# SheetPIC80_A9387.net
KiCad netlist of a schematic drawn in Altium Designer
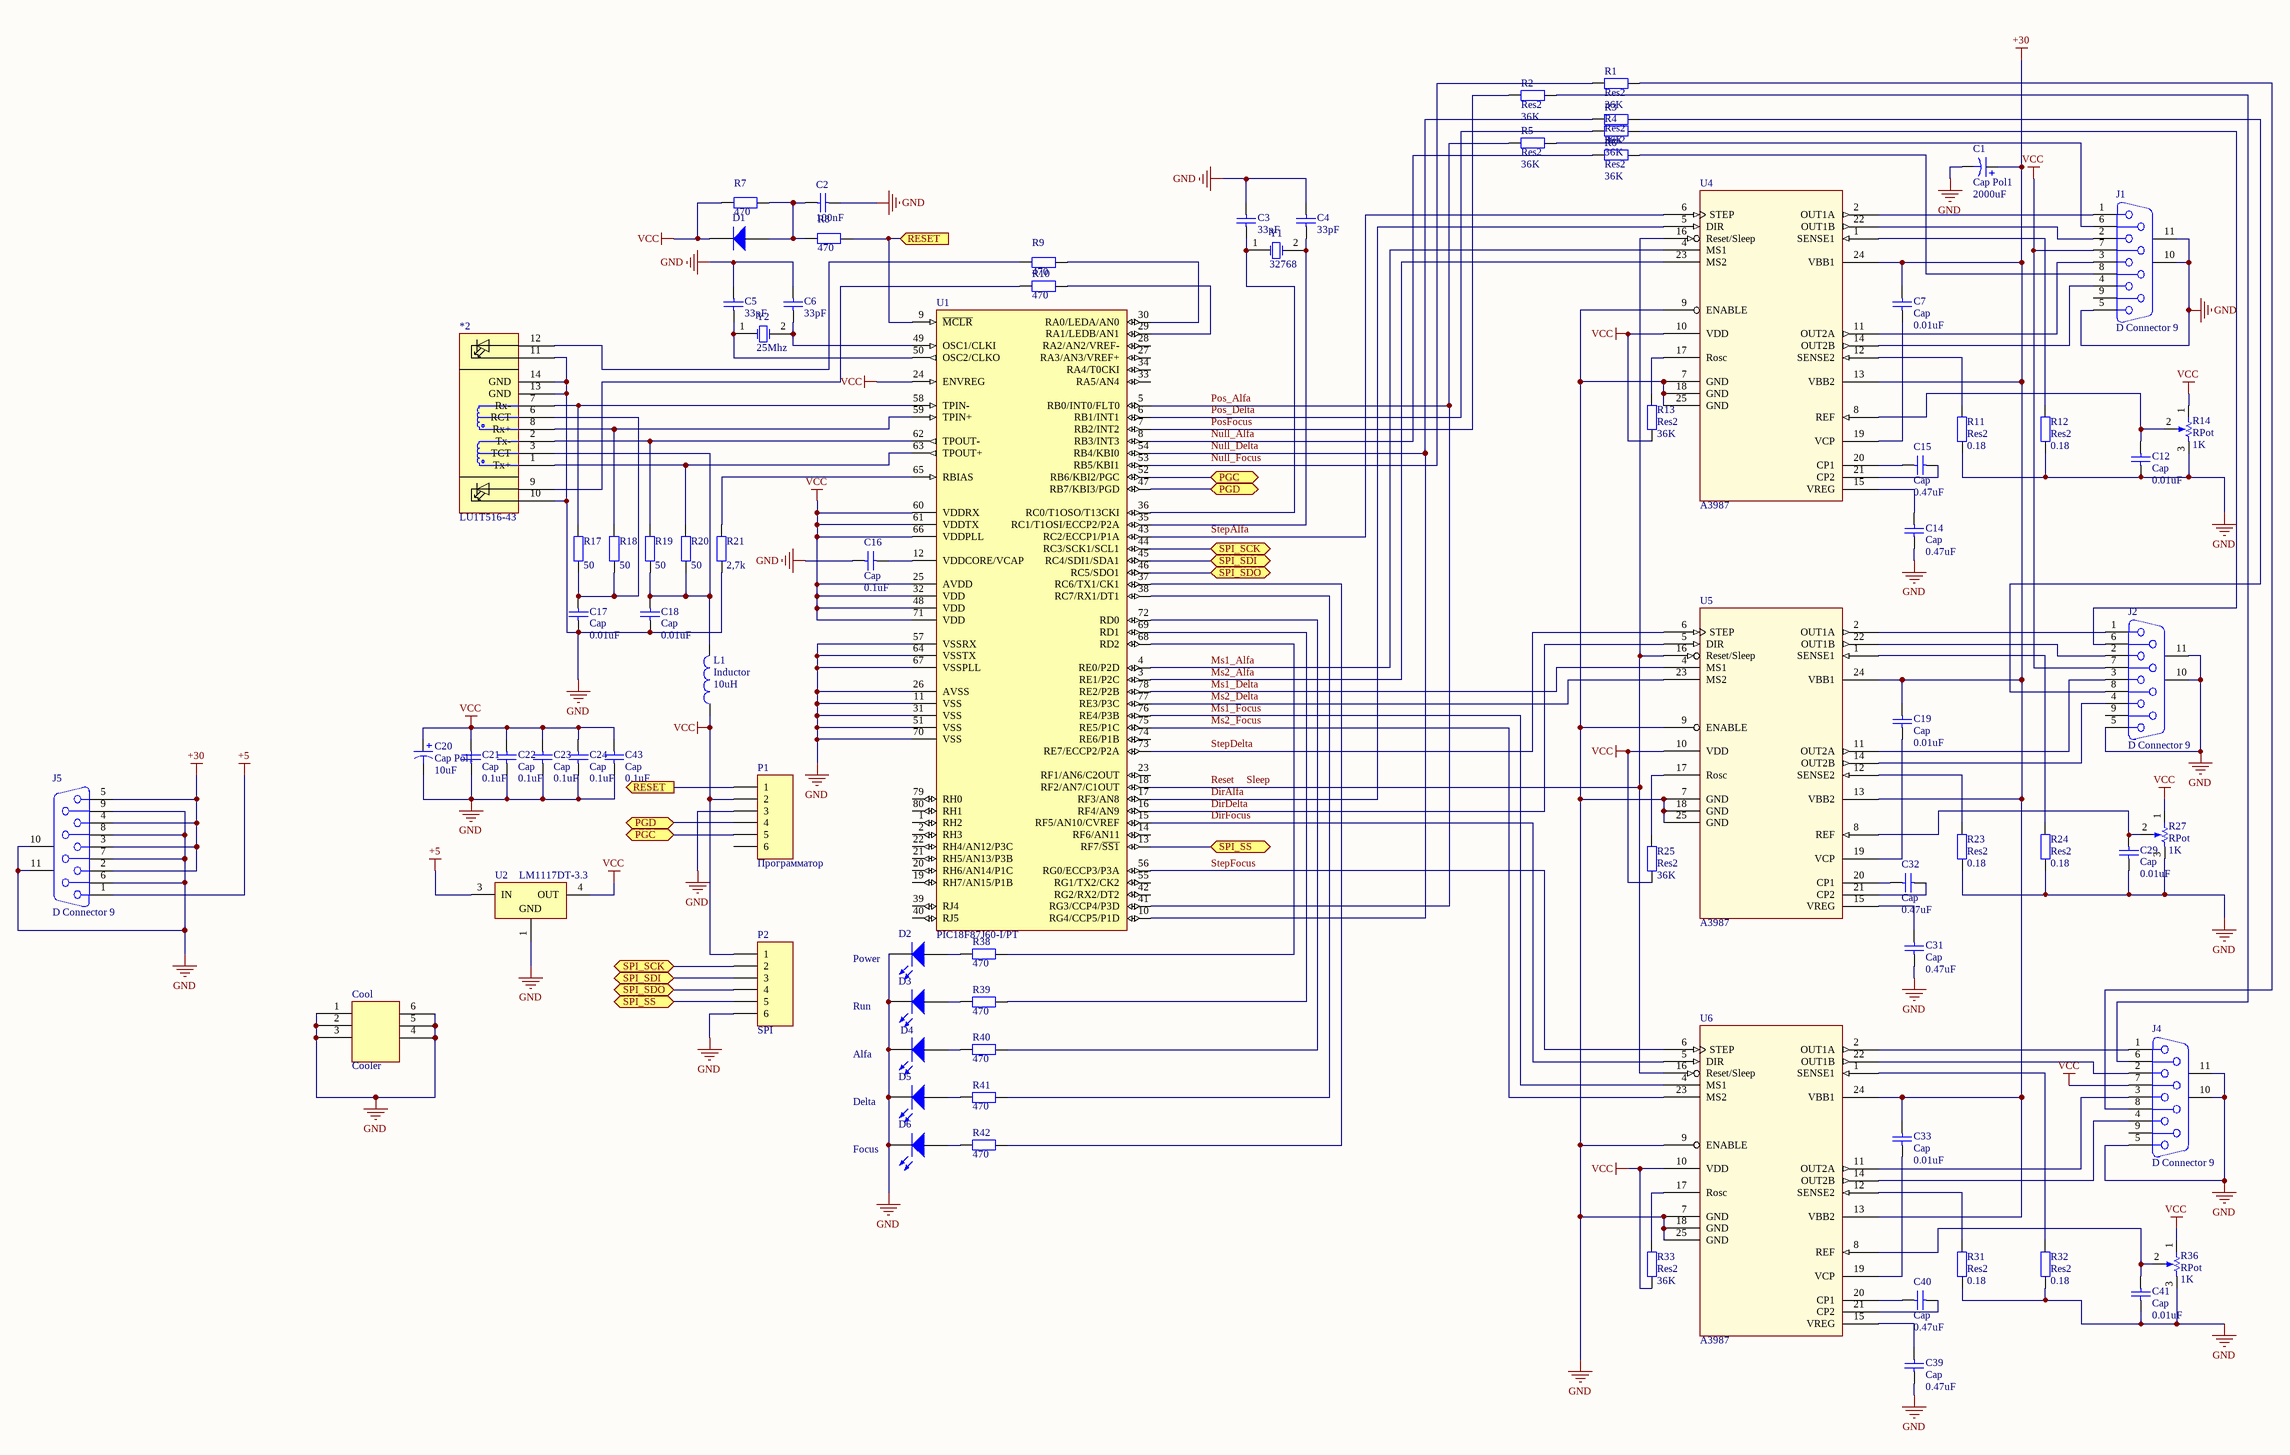
[diagram p0: SheetPIC80_A9387.SchDoc]

(export (version "E")
  (design (tool "Eeschema 10.0.6"))
  (components
    (comp (ref "*2")
      (value "LU1T516-43")
      (footprint "EthernetCON")
      (libsource (lib "Ethernet") (part "LU1T516-43"))
    )
    (comp (ref "C1")
      (value "Cap Pol1")
      (footprint "RB7.6-15")
      (description "Polarized Capacitor (Radial)")
      (fields (field (name "ALTIUM_VALUE") "2000uF"))
      (libsource (lib "Miscellaneous Devices") (part "Cap Pol1"))
    )
    (comp (ref "C2")
      (value "100nF")
      (footprint "CAPC3225N")
      (description "Capacitor")
      (fields (field (name "Comment") "Cap"))
      (libsource (lib "Miscellaneous Devices") (part "Cap"))
    )
    (comp (ref "C3")
      (value "33pF")
      (footprint "CAPC2012L")
      (description "Capacitor")
      (fields (field (name "Comment") "Cap"))
      (libsource (lib "Miscellaneous Devices") (part "Cap"))
    )
    (comp (ref "C4")
      (value "33pF")
      (footprint "CAPC2012L")
      (description "Capacitor")
      (fields (field (name "Comment") "Cap"))
      (libsource (lib "Miscellaneous Devices") (part "Cap"))
    )
    (comp (ref "C5")
      (value "33pF")
      (footprint "CAPC2012L")
      (description "Capacitor")
      (fields (field (name "Comment") "Cap"))
      (libsource (lib "Miscellaneous Devices") (part "Cap"))
    )
    (comp (ref "C6")
      (value "33pF")
      (footprint "CAPC2012L")
      (description "Capacitor")
      (fields (field (name "Comment") "Cap"))
      (libsource (lib "Miscellaneous Devices") (part "Cap"))
    )
    (comp (ref "C7")
      (value "Cap")
      (footprint "RESC3225L")
      (description "Capacitor")
      (fields (field (name "ALTIUM_VALUE") "0.01uF"))
      (libsource (lib "Miscellaneous Devices") (part "Cap"))
    )
    (comp (ref "C12")
      (value "Cap")
      (footprint "CAPC2012L")
      (description "Capacitor")
      (fields (field (name "ALTIUM_VALUE") "0.01uF"))
      (libsource (lib "Miscellaneous Devices") (part "Cap"))
    )
    (comp (ref "C14")
      (value "Cap")
      (footprint "RESC3225L")
      (description "Capacitor")
      (fields (field (name "ALTIUM_VALUE") "0.47uF"))
      (libsource (lib "Miscellaneous Devices") (part "Cap"))
    )
    (comp (ref "C15")
      (value "Cap")
      (footprint "RESC3225L")
      (description "Capacitor")
      (fields (field (name "ALTIUM_VALUE") "0.47uF"))
      (libsource (lib "Miscellaneous Devices") (part "Cap"))
    )
    (comp (ref "C16")
      (value "Cap")
      (footprint "CAPC3225L")
      (description "Capacitor")
      (fields (field (name "ALTIUM_VALUE") "0.1uF"))
      (libsource (lib "Miscellaneous Devices") (part "Cap"))
    )
    (comp (ref "C17")
      (value "Cap")
      (footprint "CAPC3216L")
      (description "Capacitor")
      (fields (field (name "ALTIUM_VALUE") "0.01uF"))
      (libsource (lib "Miscellaneous Devices") (part "Cap"))
    )
    (comp (ref "C18")
      (value "Cap")
      (footprint "CAPC3216L")
      (description "Capacitor")
      (fields (field (name "ALTIUM_VALUE") "0.01uF"))
      (libsource (lib "Miscellaneous Devices") (part "Cap"))
    )
    (comp (ref "C19")
      (value "Cap")
      (footprint "RESC3225L")
      (description "Capacitor")
      (fields (field (name "ALTIUM_VALUE") "0.01uF"))
      (libsource (lib "Miscellaneous Devices") (part "Cap"))
    )
    (comp (ref "C20")
      (value "Cap Pol1")
      (footprint "CAPPR5-5x5")
      (description "Polarized Capacitor (Radial)")
      (fields (field (name "ALTIUM_VALUE") "10uF"))
      (libsource (lib "Miscellaneous Devices") (part "Cap Pol1"))
    )
    (comp (ref "C21")
      (value "Cap")
      (footprint "CAPC3225L")
      (description "Capacitor")
      (fields (field (name "ALTIUM_VALUE") "0.1uF"))
      (libsource (lib "Miscellaneous Devices") (part "Cap"))
    )
    (comp (ref "C22")
      (value "Cap")
      (footprint "CAPC3225L")
      (description "Capacitor")
      (fields (field (name "ALTIUM_VALUE") "0.1uF"))
      (libsource (lib "Miscellaneous Devices") (part "Cap"))
    )
    (comp (ref "C23")
      (value "Cap")
      (footprint "CAPC3225L")
      (description "Capacitor")
      (fields (field (name "ALTIUM_VALUE") "0.1uF"))
      (libsource (lib "Miscellaneous Devices") (part "Cap"))
    )
    (comp (ref "C24")
      (value "Cap")
      (footprint "CAPC3225L")
      (description "Capacitor")
      (fields (field (name "ALTIUM_VALUE") "0.1uF"))
      (libsource (lib "Miscellaneous Devices") (part "Cap"))
    )
    (comp (ref "C29")
      (value "Cap")
      (footprint "CAPC2012L")
      (description "Capacitor")
      (fields (field (name "ALTIUM_VALUE") "0.01uF"))
      (libsource (lib "Miscellaneous Devices") (part "Cap"))
    )
    (comp (ref "C31")
      (value "Cap")
      (footprint "RESC3225L")
      (description "Capacitor")
      (fields (field (name "ALTIUM_VALUE") "0.47uF"))
      (libsource (lib "Miscellaneous Devices") (part "Cap"))
    )
    (comp (ref "C32")
      (value "Cap")
      (footprint "RESC3225L")
      (description "Capacitor")
      (fields (field (name "ALTIUM_VALUE") "0.47uF"))
      (libsource (lib "Miscellaneous Devices") (part "Cap"))
    )
    (comp (ref "C33")
      (value "Cap")
      (footprint "RESC3225L")
      (description "Capacitor")
      (fields (field (name "ALTIUM_VALUE") "0.01uF"))
      (libsource (lib "Miscellaneous Devices") (part "Cap"))
    )
    (comp (ref "C39")
      (value "Cap")
      (footprint "RESC3225L")
      (description "Capacitor")
      (fields (field (name "ALTIUM_VALUE") "0.47uF"))
      (libsource (lib "Miscellaneous Devices") (part "Cap"))
    )
    (comp (ref "C40")
      (value "Cap")
      (footprint "RESC3225L")
      (description "Capacitor")
      (fields (field (name "ALTIUM_VALUE") "0.47uF"))
      (libsource (lib "Miscellaneous Devices") (part "Cap"))
    )
    (comp (ref "C41")
      (value "Cap")
      (footprint "CAPC2012L")
      (description "Capacitor")
      (fields (field (name "ALTIUM_VALUE") "0.01uF"))
      (libsource (lib "Miscellaneous Devices") (part "Cap"))
    )
    (comp (ref "C43")
      (value "Cap")
      (footprint "CAPC3225L")
      (description "Capacitor")
      (fields (field (name "ALTIUM_VALUE") "0.1uF"))
      (libsource (lib "Miscellaneous Devices") (part "Cap"))
    )
    (comp (ref "Cool")
      (value "Cooler")
      (footprint "PCBComponent_1 - duplicate")
      (libsource (lib "Cooler") (part "Cooler"))
    )
    (comp (ref "D1")
      (value "Diode")
      (footprint "SOT95P240-3N")
      (description "Default Diode")
      (libsource (lib "Miscellaneous Devices") (part "Diode"))
    )
    (comp (ref "D2")
      (value "Power")
      (footprint "LED-1")
      (description "Typical RED GaAs LED")
      (libsource (lib "Miscellaneous Devices") (part "LED1"))
    )
    (comp (ref "D3")
      (value "Run")
      (footprint "LED-1")
      (description "Typical RED GaAs LED")
      (libsource (lib "Miscellaneous Devices") (part "LED1"))
    )
    (comp (ref "D4")
      (value "Alfa")
      (footprint "LED-1")
      (description "Typical RED GaAs LED")
      (libsource (lib "Miscellaneous Devices") (part "LED1"))
    )
    (comp (ref "D5")
      (value "Delta")
      (footprint "LED-1")
      (description "Typical RED GaAs LED")
      (libsource (lib "Miscellaneous Devices") (part "LED1"))
    )
    (comp (ref "D6")
      (value "Focus")
      (footprint "LED-1")
      (description "Typical RED GaAs LED")
      (libsource (lib "Miscellaneous Devices") (part "LED1"))
    )
    (comp (ref "J1")
      (value "D Connector 9")
      (footprint "D-SUB-9")
      (description "Receptacle Assembly, 9 Position, Right Angle")
      (libsource (lib "Miscellaneous Connectors") (part "D Connector 9"))
    )
    (comp (ref "J2")
      (value "D Connector 9")
      (footprint "D-SUB-9")
      (description "Receptacle Assembly, 9 Position, Right Angle")
      (libsource (lib "Miscellaneous Connectors") (part "D Connector 9"))
    )
    (comp (ref "J4")
      (value "D Connector 9")
      (footprint "D-SUB-9")
      (description "Receptacle Assembly, 9 Position, Right Angle")
      (libsource (lib "Miscellaneous Connectors") (part "D Connector 9"))
    )
    (comp (ref "J5")
      (value "D Connector 9")
      (footprint "D-SUB-9")
      (description "Receptacle Assembly, 9 Position, Right Angle")
      (libsource (lib "Miscellaneous Connectors") (part "D Connector 9"))
    )
    (comp (ref "L1")
      (value "Inductor")
      (footprint "INDC3216AL")
      (fields (field (name "ALTIUM_VALUE") "10uH"))
      (libsource (lib "Miscellaneous Devices") (part "Inductor"))
    )
    (comp (ref "P1")
      (value "Программатор")
      (footprint "HDR1X6")
      (description "Header, 6-Pin")
      (libsource (lib "Miscellaneous Connectors") (part "Header 6"))
    )
    (comp (ref "P2")
      (value "SPI")
      (footprint "HDR1X6")
      (description "Header, 6-Pin")
      (libsource (lib "Miscellaneous Connectors") (part "Header 6"))
    )
    (comp (ref "R1")
      (value "Res2")
      (footprint "RESC2012N")
      (description "Resistor")
      (fields (field (name "ALTIUM_VALUE") "36K"))
      (libsource (lib "Miscellaneous Devices") (part "Res2"))
    )
    (comp (ref "R2")
      (value "Res2")
      (footprint "RESC2012N")
      (description "Resistor")
      (fields (field (name "ALTIUM_VALUE") "36K"))
      (libsource (lib "Miscellaneous Devices") (part "Res2"))
    )
    (comp (ref "R3")
      (value "Res2")
      (footprint "RESC2012N")
      (description "Resistor")
      (fields (field (name "ALTIUM_VALUE") "36K"))
      (libsource (lib "Miscellaneous Devices") (part "Res2"))
    )
    (comp (ref "R4")
      (value "Res2")
      (footprint "RESC2012N")
      (description "Resistor")
      (fields (field (name "ALTIUM_VALUE") "36K"))
      (libsource (lib "Miscellaneous Devices") (part "Res2"))
    )
    (comp (ref "R5")
      (value "Res2")
      (footprint "RESC2012N")
      (description "Resistor")
      (fields (field (name "ALTIUM_VALUE") "36K"))
      (libsource (lib "Miscellaneous Devices") (part "Res2"))
    )
    (comp (ref "R6")
      (value "Res2")
      (footprint "RESC2012N")
      (description "Resistor")
      (fields (field (name "ALTIUM_VALUE") "36K"))
      (libsource (lib "Miscellaneous Devices") (part "Res2"))
    )
    (comp (ref "R7")
      (value "470")
      (footprint "RESC2012M")
      (description "Resistor")
      (fields (field (name "Comment") "Res2"))
      (libsource (lib "Miscellaneous Devices") (part "Res2"))
    )
    (comp (ref "R8")
      (value "470")
      (footprint "RESC2012M")
      (description "Resistor")
      (fields (field (name "Comment") "Res2"))
      (libsource (lib "Miscellaneous Devices") (part "Res2"))
    )
    (comp (ref "R9")
      (value "470")
      (footprint "RESC2012M")
      (description "Resistor")
      (fields (field (name "Comment") "Res2"))
      (libsource (lib "Miscellaneous Devices") (part "Res2"))
    )
    (comp (ref "R10")
      (value "470")
      (footprint "RESC2012M")
      (description "Resistor")
      (fields (field (name "Comment") "Res2"))
      (libsource (lib "Miscellaneous Devices") (part "Res2"))
    )
    (comp (ref "R11")
      (value "Res2")
      (footprint "RESC6332L")
      (description "Resistor")
      (fields (field (name "ALTIUM_VALUE") "0.18"))
      (libsource (lib "") (part "Res2_1"))
    )
    (comp (ref "R12")
      (value "Res2")
      (footprint "RESC6332L")
      (description "Resistor")
      (fields (field (name "ALTIUM_VALUE") "0.18"))
      (libsource (lib "") (part "Res2_1"))
    )
    (comp (ref "R13")
      (value "Res2")
      (footprint "RESC2012N")
      (description "Resistor")
      (fields (field (name "ALTIUM_VALUE") "36K"))
      (libsource (lib "") (part "Res2_1"))
    )
    (comp (ref "R14")
      (value "RPot")
      (footprint "VR5")
      (description "Potentiometer")
      (fields (field (name "ALTIUM_VALUE") "1K"))
      (libsource (lib "Miscellaneous Devices") (part "RPot"))
    )
    (comp (ref "R17")
      (value "50")
      (footprint "RESC2012M")
      (description "Resistor")
      (fields (field (name "Comment") "Res2"))
      (libsource (lib "") (part "Res2_1"))
    )
    (comp (ref "R18")
      (value "50")
      (footprint "RESC2012M")
      (description "Resistor")
      (fields (field (name "Comment") "Res2"))
      (libsource (lib "") (part "Res2_1"))
    )
    (comp (ref "R19")
      (value "50")
      (footprint "RESC2012M")
      (description "Resistor")
      (fields (field (name "Comment") "Res2"))
      (libsource (lib "") (part "Res2_1"))
    )
    (comp (ref "R20")
      (value "50")
      (footprint "RESC2012M")
      (description "Resistor")
      (fields (field (name "Comment") "Res2"))
      (libsource (lib "") (part "Res2_1"))
    )
    (comp (ref "R21")
      (value "2,7k")
      (footprint "RESC2012M")
      (description "Resistor")
      (fields (field (name "Comment") "Res2"))
      (libsource (lib "") (part "Res2_1"))
    )
    (comp (ref "R23")
      (value "Res2")
      (footprint "RESC6332L")
      (description "Resistor")
      (fields (field (name "ALTIUM_VALUE") "0.18"))
      (libsource (lib "") (part "Res2_1"))
    )
    (comp (ref "R24")
      (value "Res2")
      (footprint "RESC6332L")
      (description "Resistor")
      (fields (field (name "ALTIUM_VALUE") "0.18"))
      (libsource (lib "") (part "Res2_1"))
    )
    (comp (ref "R25")
      (value "Res2")
      (footprint "RESC2012N")
      (description "Resistor")
      (fields (field (name "ALTIUM_VALUE") "36K"))
      (libsource (lib "") (part "Res2_1"))
    )
    (comp (ref "R27")
      (value "RPot")
      (footprint "VR5")
      (description "Potentiometer")
      (fields (field (name "ALTIUM_VALUE") "1K"))
      (libsource (lib "Miscellaneous Devices") (part "RPot"))
    )
    (comp (ref "R31")
      (value "Res2")
      (footprint "RESC6332L")
      (description "Resistor")
      (fields (field (name "ALTIUM_VALUE") "0.18"))
      (libsource (lib "") (part "Res2_1"))
    )
    (comp (ref "R32")
      (value "Res2")
      (footprint "RESC6332L")
      (description "Resistor")
      (fields (field (name "ALTIUM_VALUE") "0.18"))
      (libsource (lib "") (part "Res2_1"))
    )
    (comp (ref "R33")
      (value "Res2")
      (footprint "RESC2012N")
      (description "Resistor")
      (fields (field (name "ALTIUM_VALUE") "36K"))
      (libsource (lib "") (part "Res2_1"))
    )
    (comp (ref "R36")
      (value "RPot")
      (footprint "VR5")
      (description "Potentiometer")
      (fields (field (name "ALTIUM_VALUE") "1K"))
      (libsource (lib "Miscellaneous Devices") (part "RPot"))
    )
    (comp (ref "R38")
      (value "470")
      (footprint "RESC2012M")
      (description "Resistor")
      (fields (field (name "Comment") "Res2"))
      (libsource (lib "Miscellaneous Devices") (part "Res2"))
    )
    (comp (ref "R39")
      (value "470")
      (footprint "RESC2012M")
      (description "Resistor")
      (fields (field (name "Comment") "Res2"))
      (libsource (lib "Miscellaneous Devices") (part "Res2"))
    )
    (comp (ref "R40")
      (value "470")
      (footprint "RESC2012M")
      (description "Resistor")
      (fields (field (name "Comment") "Res2"))
      (libsource (lib "Miscellaneous Devices") (part "Res2"))
    )
    (comp (ref "R41")
      (value "470")
      (footprint "RESC2012M")
      (description "Resistor")
      (fields (field (name "Comment") "Res2"))
      (libsource (lib "Miscellaneous Devices") (part "Res2"))
    )
    (comp (ref "R42")
      (value "470")
      (footprint "RESC2012M")
      (description "Resistor")
      (fields (field (name "Comment") "Res2"))
      (libsource (lib "Miscellaneous Devices") (part "Res2"))
    )
    (comp (ref "U1")
      (value "PIC18F87J60-I/PT")
      (footprint "TQFP-PT80_N")
      (libsource (lib "Microchip Microcontroller 8-Bit PIC18") (part "PIC18F87J60-I/PT"))
    )
    (comp (ref "U2")
      (value "LM1117DT-3.3")
      (footprint "TD03B_N")
      (description "800mA Low-Dropout Linear Regulator")
      (fields
        (field (name "MANUFACTURER") "National Semiconductor")
        (field (name "DIGIKEYPARTNUMBER") "LM1117DT-3.3-ND")
      )
      (libsource (lib "NSC LDO") (part "LM1117DT-3.3"))
    )
    (comp (ref "U4")
      (value "A3987")
      (footprint "TSOP65P640_HS-24AM - duplicate")
      (description "Stepper Controller")
      (libsource (lib "Allegro Stepper Control") (part "A3987"))
    )
    (comp (ref "U5")
      (value "A3987")
      (footprint "TSOP65P640_HS-24AM - duplicate")
      (description "Stepper Controller")
      (libsource (lib "Allegro Stepper Control") (part "A3987"))
    )
    (comp (ref "U6")
      (value "A3987")
      (footprint "TSOP65P640_HS-24AM - duplicate")
      (description "Stepper Controller")
      (libsource (lib "Allegro Stepper Control") (part "A3987"))
    )
    (comp (ref "Y1")
      (value "32768")
      (footprint "Quartz")
      (description "Crystal Oscillator")
      (fields (field (name "Comment") "XTAL"))
      (libsource (lib "Miscellaneous Devices") (part "XTAL"))
    )
    (comp (ref "Y2")
      (value "25Mhz")
      (footprint "Quartz")
      (description "Crystal Oscillator")
      (fields (field (name "Comment") "XTAL"))
      (libsource (lib "Miscellaneous Devices") (part "XTAL"))
    )
  )
  (nets
    (net (code "1") (name "+5") (class "Default")
      (node (ref "J5") (pin "1") (pinfunction "1_1") (pintype "passive"))
      (node (ref "U2") (pin "3") (pinfunction "IN_3") (pintype "power_in"))
    )
    (net (code "2") (name "+30") (class "Default")
      (node (ref "C1") (pin "1") (pinfunction "1_1") (pintype "passive"))
      (node (ref "C19") (pin "2") (pinfunction "2_2") (pintype "passive"))
      (node (ref "C33") (pin "2") (pinfunction "2_2") (pintype "passive"))
      (node (ref "C7") (pin "2") (pinfunction "2_2") (pintype "passive"))
      (node (ref "J5") (pin "2") (pinfunction "2_2") (pintype "passive"))
      (node (ref "J5") (pin "3") (pinfunction "3_3") (pintype "passive"))
      (node (ref "J5") (pin "4") (pinfunction "4_4") (pintype "passive"))
      (node (ref "J5") (pin "5") (pinfunction "5_5") (pintype "passive"))
      (node (ref "U4") (pin "13") (pinfunction "VBB2_13") (pintype "power_in"))
      (node (ref "U4") (pin "24") (pinfunction "VBB1_24") (pintype "power_in"))
      (node (ref "U5") (pin "13") (pinfunction "VBB2_13") (pintype "power_in"))
      (node (ref "U5") (pin "24") (pinfunction "VBB1_24") (pintype "power_in"))
      (node (ref "U6") (pin "13") (pinfunction "VBB2_13") (pintype "power_in"))
      (node (ref "U6") (pin "24") (pinfunction "VBB1_24") (pintype "power_in"))
    )
    (net (code "3") (name "/DirAlfa") (class "Default")
      (node (ref "U1") (pin "17") (pinfunction "RF3/AN8_17") (pintype "bidirectional"))
      (node (ref "U4") (pin "5") (pinfunction "DIR_5") (pintype "input"))
    )
    (net (code "4") (name "/DirDelta") (class "Default")
      (node (ref "U1") (pin "16") (pinfunction "RF4/AN9_16") (pintype "bidirectional"))
      (node (ref "U5") (pin "5") (pinfunction "DIR_5") (pintype "input"))
    )
    (net (code "5") (name "/DirFocus") (class "Default")
      (node (ref "U1") (pin "15") (pinfunction "RF5/AN10/CVREF_15") (pintype "bidirectional"))
      (node (ref "U6") (pin "5") (pinfunction "DIR_5") (pintype "input"))
    )
    (net (code "6") (name "/Ms1_Alfa") (class "Default")
      (node (ref "U1") (pin "4") (pinfunction "RE0/P2D_4") (pintype "bidirectional"))
      (node (ref "U4") (pin "4") (pinfunction "MS1_4") (pintype "passive"))
    )
    (net (code "7") (name "/Ms1_Delta") (class "Default")
      (node (ref "U1") (pin "78") (pinfunction "RE2/P2B_78") (pintype "bidirectional"))
      (node (ref "U5") (pin "4") (pinfunction "MS1_4") (pintype "passive"))
    )
    (net (code "8") (name "/Ms1_Focus") (class "Default")
      (node (ref "U1") (pin "76") (pinfunction "RE4/P3B_76") (pintype "bidirectional"))
      (node (ref "U6") (pin "4") (pinfunction "MS1_4") (pintype "passive"))
    )
    (net (code "9") (name "/Ms2_Alfa") (class "Default")
      (node (ref "U1") (pin "3") (pinfunction "RE1/P2C_3") (pintype "bidirectional"))
      (node (ref "U4") (pin "23") (pinfunction "MS2_23") (pintype "passive"))
    )
    (net (code "10") (name "/Ms2_Delta") (class "Default")
      (node (ref "U1") (pin "77") (pinfunction "RE3/P3C_77") (pintype "bidirectional"))
      (node (ref "U5") (pin "23") (pinfunction "MS2_23") (pintype "passive"))
    )
    (net (code "11") (name "/Ms2_Focus") (class "Default")
      (node (ref "U1") (pin "75") (pinfunction "RE5/P1C_75") (pintype "bidirectional"))
      (node (ref "U6") (pin "23") (pinfunction "MS2_23") (pintype "passive"))
    )
    (net (code "12") (name "/Null_Alfa") (class "Default")
      (node (ref "R6") (pin "2") (pinfunction "2_2") (pintype "passive"))
      (node (ref "U1") (pin "8") (pinfunction "RB3/INT3_8") (pintype "bidirectional"))
    )
    (net (code "13") (name "/Null_Delta") (class "Default")
      (node (ref "R3") (pin "2") (pinfunction "2_2") (pintype "passive"))
      (node (ref "U1") (pin "10") (pinfunction "RG4/CCP5/P1D_10") (pintype "bidirectional"))
      (node (ref "U1") (pin "54") (pinfunction "RB4/KBI0_54") (pintype "bidirectional"))
    )
    (net (code "14") (name "/Null_Focus") (class "Default")
      (node (ref "R1") (pin "2") (pinfunction "2_2") (pintype "passive"))
      (node (ref "U1") (pin "53") (pinfunction "RB5/KBI1_53") (pintype "bidirectional"))
    )
    (net (code "15") (name "/PGC") (class "Default")
      (node (ref "P1") (pin "5") (pinfunction "5_5") (pintype "passive"))
      (node (ref "U1") (pin "52") (pinfunction "RB6/KBI2/PGC_52") (pintype "bidirectional"))
    )
    (net (code "16") (name "/PGD") (class "Default")
      (node (ref "P1") (pin "4") (pinfunction "4_4") (pintype "passive"))
      (node (ref "U1") (pin "47") (pinfunction "RB7/KBI3/PGD_47") (pintype "bidirectional"))
    )
    (net (code "17") (name "/PosFocus") (class "Default")
      (node (ref "R2") (pin "2") (pinfunction "2_2") (pintype "passive"))
      (node (ref "U1") (pin "7") (pinfunction "RB2/INT2_7") (pintype "bidirectional"))
    )
    (net (code "18") (name "/Pos_Alfa") (class "Default")
      (node (ref "R5") (pin "2") (pinfunction "2_2") (pintype "passive"))
      (node (ref "U1") (pin "41") (pinfunction "RG3/CCP4/P3D_41") (pintype "bidirectional"))
      (node (ref "U1") (pin "5") (pinfunction "RB0/INT0/FLT0_5") (pintype "bidirectional"))
    )
    (net (code "19") (name "/Pos_Delta") (class "Default")
      (node (ref "R4") (pin "2") (pinfunction "2_2") (pintype "passive"))
      (node (ref "U1") (pin "6") (pinfunction "RB1/INT1_6") (pintype "bidirectional"))
    )
    (net (code "20") (name "/RESET") (class "Default")
      (node (ref "P1") (pin "1") (pinfunction "1_1") (pintype "passive"))
      (node (ref "R8") (pin "1") (pinfunction "1_1") (pintype "passive"))
      (node (ref "U1") (pin "9") (pinfunction "~{MCLR}_9") (pintype "input"))
    )
    (net (code "21") (name "/Reset") (class "Default")
      (node (ref "U1") (pin "18") (pinfunction "RF2/AN7/C1OUT_18") (pintype "bidirectional"))
      (node (ref "U4") (pin "16") (pinfunction "Reset/Sleep_16") (pintype "input"))
      (node (ref "U5") (pin "16") (pinfunction "Reset/Sleep_16") (pintype "input"))
      (node (ref "U6") (pin "16") (pinfunction "Reset/Sleep_16") (pintype "input"))
    )
    (net (code "22") (name "/SPI_SCK") (class "Default")
      (node (ref "P2") (pin "2") (pinfunction "2_2") (pintype "passive"))
      (node (ref "U1") (pin "44") (pinfunction "RC3/SCK1/SCL1_44") (pintype "bidirectional"))
    )
    (net (code "23") (name "/SPI_SDI") (class "Default")
      (node (ref "P2") (pin "3") (pinfunction "3_3") (pintype "passive"))
      (node (ref "U1") (pin "45") (pinfunction "RC4/SDI1/SDA1_45") (pintype "bidirectional"))
    )
    (net (code "24") (name "/SPI_SDO") (class "Default")
      (node (ref "P2") (pin "4") (pinfunction "4_4") (pintype "passive"))
      (node (ref "U1") (pin "46") (pinfunction "RC5/SDO1_46") (pintype "bidirectional"))
    )
    (net (code "25") (name "/SPI_SS") (class "Default")
      (node (ref "P2") (pin "5") (pinfunction "5_5") (pintype "passive"))
      (node (ref "U1") (pin "13") (pinfunction "RF7/~{SS1}_13") (pintype "bidirectional"))
    )
    (net (code "26") (name "/StepAlfa") (class "Default")
      (node (ref "U1") (pin "43") (pinfunction "RC2/ECCP1/P1A_43") (pintype "bidirectional"))
      (node (ref "U4") (pin "6") (pinfunction "STEP_6") (pintype "input"))
    )
    (net (code "27") (name "/StepDelta") (class "Default")
      (node (ref "U1") (pin "73") (pinfunction "RE7/ECCP2/P2A_73") (pintype "bidirectional"))
      (node (ref "U5") (pin "6") (pinfunction "STEP_6") (pintype "input"))
    )
    (net (code "28") (name "/StepFocus") (class "Default")
      (node (ref "U1") (pin "56") (pinfunction "RG0/ECCP3/P3A_56") (pintype "bidirectional"))
      (node (ref "U6") (pin "6") (pinfunction "STEP_6") (pintype "input"))
    )
    (net (code "29") (name "GND") (class "Default")
      (node (ref "*2") (pin "10") (pintype "passive"))
      (node (ref "*2") (pin "11") (pintype "passive"))
      (node (ref "*2") (pin "13") (pinfunction "GND_13") (pintype "passive"))
      (node (ref "*2") (pin "14") (pinfunction "GND_14") (pintype "passive"))
      (node (ref "C1") (pin "2") (pinfunction "2_2") (pintype "passive"))
      (node (ref "C12") (pin "1") (pinfunction "1_1") (pintype "passive"))
      (node (ref "C14") (pin "1") (pinfunction "1_1") (pintype "passive"))
      (node (ref "C16") (pin "2") (pinfunction "2_2") (pintype "passive"))
      (node (ref "C17") (pin "1") (pinfunction "1_1") (pintype "passive"))
      (node (ref "C18") (pin "1") (pinfunction "1_1") (pintype "passive"))
      (node (ref "C2") (pin "1") (pinfunction "1_1") (pintype "passive"))
      (node (ref "C20") (pin "2") (pinfunction "2_2") (pintype "passive"))
      (node (ref "C21") (pin "2") (pinfunction "2_2") (pintype "passive"))
      (node (ref "C22") (pin "2") (pinfunction "2_2") (pintype "passive"))
      (node (ref "C23") (pin "2") (pinfunction "2_2") (pintype "passive"))
      (node (ref "C24") (pin "2") (pinfunction "2_2") (pintype "passive"))
      (node (ref "C29") (pin "1") (pinfunction "1_1") (pintype "passive"))
      (node (ref "C3") (pin "2") (pinfunction "2_2") (pintype "passive"))
      (node (ref "C31") (pin "1") (pinfunction "1_1") (pintype "passive"))
      (node (ref "C39") (pin "1") (pinfunction "1_1") (pintype "passive"))
      (node (ref "C4") (pin "1") (pinfunction "1_1") (pintype "passive"))
      (node (ref "C41") (pin "1") (pinfunction "1_1") (pintype "passive"))
      (node (ref "C43") (pin "2") (pinfunction "2_2") (pintype "passive"))
      (node (ref "C5") (pin "2") (pinfunction "2_2") (pintype "passive"))
      (node (ref "C6") (pin "1") (pinfunction "1_1") (pintype "passive"))
      (node (ref "Cool") (pin "1") (pintype "passive"))
      (node (ref "Cool") (pin "2") (pintype "passive"))
      (node (ref "Cool") (pin "3") (pintype "passive"))
      (node (ref "Cool") (pin "4") (pintype "passive"))
      (node (ref "Cool") (pin "5") (pintype "passive"))
      (node (ref "Cool") (pin "6") (pintype "passive"))
      (node (ref "D2") (pin "2") (pinfunction "K_2") (pintype "passive"))
      (node (ref "D3") (pin "2") (pinfunction "K_2") (pintype "passive"))
      (node (ref "D4") (pin "2") (pinfunction "K_2") (pintype "passive"))
      (node (ref "D5") (pin "2") (pinfunction "K_2") (pintype "passive"))
      (node (ref "D6") (pin "2") (pinfunction "K_2") (pintype "passive"))
      (node (ref "J1") (pin "10") (pinfunction "MH1_10") (pintype "passive"))
      (node (ref "J1") (pin "11") (pinfunction "MH2_11") (pintype "passive"))
      (node (ref "J1") (pin "5") (pinfunction "5_5") (pintype "passive"))
      (node (ref "J2") (pin "10") (pinfunction "MH1_10") (pintype "passive"))
      (node (ref "J2") (pin "11") (pinfunction "MH2_11") (pintype "passive"))
      (node (ref "J2") (pin "5") (pinfunction "5_5") (pintype "passive"))
      (node (ref "J4") (pin "10") (pinfunction "MH1_10") (pintype "passive"))
      (node (ref "J4") (pin "11") (pinfunction "MH2_11") (pintype "passive"))
      (node (ref "J4") (pin "5") (pinfunction "5_5") (pintype "passive"))
      (node (ref "J5") (pin "10") (pinfunction "MH1_10") (pintype "passive"))
      (node (ref "J5") (pin "11") (pinfunction "MH2_11") (pintype "passive"))
      (node (ref "J5") (pin "6") (pinfunction "6_6") (pintype "passive"))
      (node (ref "J5") (pin "7") (pinfunction "7_7") (pintype "passive"))
      (node (ref "J5") (pin "8") (pinfunction "8_8") (pintype "passive"))
      (node (ref "J5") (pin "9") (pinfunction "9_9") (pintype "passive"))
      (node (ref "P1") (pin "3") (pinfunction "3_3") (pintype "passive"))
      (node (ref "P2") (pin "6") (pinfunction "6_6") (pintype "passive"))
      (node (ref "R11") (pin "1") (pinfunction "1_1") (pintype "passive"))
      (node (ref "R12") (pin "1") (pinfunction "1_1") (pintype "passive"))
      (node (ref "R14") (pin "3") (pinfunction "BOT_3") (pintype "passive"))
      (node (ref "R21") (pin "1") (pinfunction "1_1") (pintype "passive"))
      (node (ref "R23") (pin "1") (pinfunction "1_1") (pintype "passive"))
      (node (ref "R24") (pin "1") (pinfunction "1_1") (pintype "passive"))
      (node (ref "R27") (pin "3") (pinfunction "BOT_3") (pintype "passive"))
      (node (ref "R31") (pin "1") (pinfunction "1_1") (pintype "passive"))
      (node (ref "R32") (pin "1") (pinfunction "1_1") (pintype "passive"))
      (node (ref "R36") (pin "3") (pinfunction "BOT_3") (pintype "passive"))
      (node (ref "U1") (pin "11") (pinfunction "VSS_11") (pintype "power_in"))
      (node (ref "U1") (pin "26") (pinfunction "AVSS_26") (pintype "power_in"))
      (node (ref "U1") (pin "31") (pinfunction "VSS_31") (pintype "power_in"))
      (node (ref "U1") (pin "51") (pinfunction "VSS_51") (pintype "power_in"))
      (node (ref "U1") (pin "57") (pinfunction "VSSRX_57") (pintype "power_in"))
      (node (ref "U1") (pin "64") (pinfunction "VSSTX_64") (pintype "power_in"))
      (node (ref "U1") (pin "67") (pinfunction "VSSPLL_67") (pintype "power_in"))
      (node (ref "U1") (pin "70") (pinfunction "VSS_70") (pintype "power_in"))
      (node (ref "U2") (pin "1") (pinfunction "GND_1") (pintype "power_in"))
      (node (ref "U4") (pin "18") (pinfunction "GND_18") (pintype "power_in"))
      (node (ref "U4") (pin "25") (pinfunction "GND_25") (pintype "power_in"))
      (node (ref "U4") (pin "7") (pinfunction "GND_7") (pintype "power_in"))
      (node (ref "U4") (pin "9") (pinfunction "ENABLE_9") (pintype "passive"))
      (node (ref "U5") (pin "18") (pinfunction "GND_18") (pintype "power_in"))
      (node (ref "U5") (pin "25") (pinfunction "GND_25") (pintype "power_in"))
      (node (ref "U5") (pin "7") (pinfunction "GND_7") (pintype "power_in"))
      (node (ref "U5") (pin "9") (pinfunction "ENABLE_9") (pintype "passive"))
      (node (ref "U6") (pin "18") (pinfunction "GND_18") (pintype "power_in"))
      (node (ref "U6") (pin "25") (pinfunction "GND_25") (pintype "power_in"))
      (node (ref "U6") (pin "7") (pinfunction "GND_7") (pintype "power_in"))
      (node (ref "U6") (pin "9") (pinfunction "ENABLE_9") (pintype "passive"))
    )
    (net (code "30") (name "Net-(*2-Pad9)") (class "Default")
      (node (ref "*2") (pin "9") (pintype "passive"))
      (node (ref "R10") (pin "2") (pinfunction "2_2") (pintype "passive"))
    )
    (net (code "31") (name "Net-(*2-Pad12)") (class "Default")
      (node (ref "*2") (pin "12") (pintype "passive"))
      (node (ref "R9") (pin "2") (pinfunction "2_2") (pintype "passive"))
    )
    (net (code "32") (name "Net-(*2-RCT)") (class "Default")
      (node (ref "*2") (pin "6") (pinfunction "RCT_6") (pintype "passive"))
      (node (ref "C17") (pin "2") (pinfunction "2_2") (pintype "passive"))
      (node (ref "R17") (pin "1") (pinfunction "1_1") (pintype "passive"))
      (node (ref "R18") (pin "1") (pinfunction "1_1") (pintype "passive"))
    )
    (net (code "33") (name "Net-(*2-Rx+)") (class "Default")
      (node (ref "*2") (pin "8") (pinfunction "Rx+_8") (pintype "passive"))
      (node (ref "R18") (pin "2") (pinfunction "2_2") (pintype "passive"))
      (node (ref "U1") (pin "59") (pinfunction "TPIN+_59") (pintype "input"))
    )
    (net (code "34") (name "Net-(*2-Rx-)") (class "Default")
      (node (ref "*2") (pin "7") (pinfunction "Rx-_7") (pintype "passive"))
      (node (ref "R17") (pin "2") (pinfunction "2_2") (pintype "passive"))
      (node (ref "U1") (pin "58") (pinfunction "TPIN-_58") (pintype "input"))
    )
    (net (code "35") (name "Net-(*2-TCT)") (class "Default")
      (node (ref "*2") (pin "3") (pinfunction "TCT_3") (pintype "passive"))
      (node (ref "C18") (pin "2") (pinfunction "2_2") (pintype "passive"))
      (node (ref "L1") (pin "2") (pinfunction "2_2") (pintype "passive"))
      (node (ref "R19") (pin "1") (pinfunction "1_1") (pintype "passive"))
      (node (ref "R20") (pin "1") (pinfunction "1_1") (pintype "passive"))
    )
    (net (code "36") (name "Net-(*2-Tx+)") (class "Default")
      (node (ref "*2") (pin "1") (pinfunction "Tx+_1") (pintype "passive"))
      (node (ref "R20") (pin "2") (pinfunction "2_2") (pintype "passive"))
      (node (ref "U1") (pin "63") (pinfunction "TPOUT+_63") (pintype "output"))
    )
    (net (code "37") (name "Net-(*2-Tx-)") (class "Default")
      (node (ref "*2") (pin "2") (pinfunction "Tx-_2") (pintype "passive"))
      (node (ref "R19") (pin "2") (pinfunction "2_2") (pintype "passive"))
      (node (ref "U1") (pin "62") (pinfunction "TPOUT-_62") (pintype "output"))
    )
    (net (code "38") (name "Net-(D1-A)") (class "Default")
      (node (ref "C2") (pin "2") (pinfunction "2_2") (pintype "passive"))
      (node (ref "D1") (pin "1") (pinfunction "A_1") (pintype "passive"))
      (node (ref "R7") (pin "1") (pinfunction "1_1") (pintype "passive"))
      (node (ref "R8") (pin "2") (pinfunction "2_2") (pintype "passive"))
    )
    (net (code "39") (name "Net-(D2-A)") (class "Default")
      (node (ref "D2") (pin "1") (pinfunction "A_1") (pintype "passive"))
      (node (ref "R38") (pin "2") (pinfunction "2_2") (pintype "passive"))
    )
    (net (code "40") (name "Net-(D3-A)") (class "Default")
      (node (ref "D3") (pin "1") (pinfunction "A_1") (pintype "passive"))
      (node (ref "R39") (pin "2") (pinfunction "2_2") (pintype "passive"))
    )
    (net (code "41") (name "Net-(D4-A)") (class "Default")
      (node (ref "D4") (pin "1") (pinfunction "A_1") (pintype "passive"))
      (node (ref "R40") (pin "2") (pinfunction "2_2") (pintype "passive"))
    )
    (net (code "42") (name "Net-(D5-A)") (class "Default")
      (node (ref "D5") (pin "1") (pinfunction "A_1") (pintype "passive"))
      (node (ref "R41") (pin "2") (pinfunction "2_2") (pintype "passive"))
    )
    (net (code "43") (name "Net-(D6-A)") (class "Default")
      (node (ref "D6") (pin "1") (pinfunction "A_1") (pintype "passive"))
      (node (ref "R42") (pin "2") (pinfunction "2_2") (pintype "passive"))
    )
    (net (code "44") (name "Net-(J1-Pad6)") (class "Default")
      (node (ref "J1") (pin "6") (pinfunction "6_6") (pintype "passive"))
      (node (ref "R5") (pin "1") (pinfunction "1_1") (pintype "passive"))
    )
    (net (code "45") (name "Net-(J1-Pad8)") (class "Default")
      (node (ref "J1") (pin "8") (pinfunction "8_8") (pintype "passive"))
      (node (ref "R6") (pin "1") (pinfunction "1_1") (pintype "passive"))
    )
    (net (code "46") (name "Net-(J2-Pad6)") (class "Default")
      (node (ref "J2") (pin "6") (pinfunction "6_6") (pintype "passive"))
      (node (ref "R4") (pin "1") (pinfunction "1_1") (pintype "passive"))
    )
    (net (code "47") (name "Net-(J2-Pad8)") (class "Default")
      (node (ref "J2") (pin "8") (pinfunction "8_8") (pintype "passive"))
      (node (ref "R3") (pin "1") (pinfunction "1_1") (pintype "passive"))
    )
    (net (code "48") (name "Net-(J4-Pad6)") (class "Default")
      (node (ref "J4") (pin "6") (pinfunction "6_6") (pintype "passive"))
      (node (ref "R2") (pin "1") (pinfunction "1_1") (pintype "passive"))
    )
    (net (code "49") (name "Net-(J4-Pad8)") (class "Default")
      (node (ref "J4") (pin "8") (pinfunction "8_8") (pintype "passive"))
      (node (ref "R1") (pin "1") (pinfunction "1_1") (pintype "passive"))
    )
    (net (code "50") (name "Net-(R14-TAP)") (class "Default")
      (node (ref "C12") (pin "2") (pinfunction "2_2") (pintype "passive"))
      (node (ref "R14") (pin "2") (pinfunction "TAP_2") (pintype "passive"))
      (node (ref "U4") (pin "8") (pinfunction "REF_8") (pintype "input"))
    )
    (net (code "51") (name "Net-(R27-TAP)") (class "Default")
      (node (ref "C29") (pin "2") (pinfunction "2_2") (pintype "passive"))
      (node (ref "R27") (pin "2") (pinfunction "TAP_2") (pintype "passive"))
      (node (ref "U5") (pin "8") (pinfunction "REF_8") (pintype "input"))
    )
    (net (code "52") (name "Net-(R36-TAP)") (class "Default")
      (node (ref "C41") (pin "2") (pinfunction "2_2") (pintype "passive"))
      (node (ref "R36") (pin "2") (pinfunction "TAP_2") (pintype "passive"))
      (node (ref "U6") (pin "8") (pinfunction "REF_8") (pintype "input"))
    )
    (net (code "53") (name "Net-(U1-OSC1{slash}CLKI)") (class "Default")
      (node (ref "C6") (pin "2") (pinfunction "2_2") (pintype "passive"))
      (node (ref "U1") (pin "49") (pinfunction "OSC1/CLKI_49") (pintype "input"))
      (node (ref "Y2") (pin "2") (pinfunction "OSC2_2") (pintype "passive"))
    )
    (net (code "54") (name "Net-(U1-OSC2{slash}CLKO)") (class "Default")
      (node (ref "C5") (pin "1") (pinfunction "1_1") (pintype "passive"))
      (node (ref "U1") (pin "50") (pinfunction "OSC2/CLKO_50") (pintype "output"))
      (node (ref "Y2") (pin "1") (pinfunction "OSC1_1") (pintype "passive"))
    )
    (net (code "55") (name "Net-(U1-RA0{slash}LEDA{slash}AN0)") (class "Default")
      (node (ref "R9") (pin "1") (pinfunction "1_1") (pintype "passive"))
      (node (ref "U1") (pin "30") (pinfunction "RA0/LEDA/AN0_30") (pintype "bidirectional"))
    )
    (net (code "56") (name "Net-(U1-RA1{slash}LEDB{slash}AN1)") (class "Default")
      (node (ref "R10") (pin "1") (pinfunction "1_1") (pintype "passive"))
      (node (ref "U1") (pin "29") (pinfunction "RA1/LEDB/AN1_29") (pintype "bidirectional"))
    )
    (net (code "57") (name "Net-(U1-RBIAS)") (class "Default")
      (node (ref "R21") (pin "2") (pinfunction "2_2") (pintype "passive"))
      (node (ref "U1") (pin "65") (pinfunction "RBIAS_65") (pintype "input"))
    )
    (net (code "58") (name "Net-(U1-RC0{slash}T1OSO{slash}T13CKI)") (class "Default")
      (node (ref "C3") (pin "1") (pinfunction "1_1") (pintype "passive"))
      (node (ref "U1") (pin "36") (pinfunction "RC0/T1OSO/T13CKI_36") (pintype "bidirectional"))
      (node (ref "Y1") (pin "1") (pinfunction "OSC1_1") (pintype "passive"))
    )
    (net (code "59") (name "Net-(U1-RC1{slash}T1OSI{slash}ECCP2{slash}P2A)") (class "Default")
      (node (ref "C4") (pin "2") (pinfunction "2_2") (pintype "passive"))
      (node (ref "U1") (pin "35") (pinfunction "RC1/T1OSI/ECCP2/P2A_35") (pintype "bidirectional"))
      (node (ref "Y1") (pin "2") (pinfunction "OSC2_2") (pintype "passive"))
    )
    (net (code "60") (name "Net-(U1-RC6{slash}TX1{slash}CK1)") (class "Default")
      (node (ref "R42") (pin "1") (pinfunction "1_1") (pintype "passive"))
      (node (ref "U1") (pin "37") (pinfunction "RC6/TX1/CK1_37") (pintype "bidirectional"))
    )
    (net (code "61") (name "Net-(U1-RC7{slash}RX1{slash}DT1)") (class "Default")
      (node (ref "R41") (pin "1") (pinfunction "1_1") (pintype "passive"))
      (node (ref "U1") (pin "38") (pinfunction "RC7/RX1/DT1_38") (pintype "bidirectional"))
    )
    (net (code "62") (name "Net-(U1-RD0)") (class "Default")
      (node (ref "R40") (pin "1") (pinfunction "1_1") (pintype "passive"))
      (node (ref "U1") (pin "72") (pinfunction "RD0_72") (pintype "bidirectional"))
    )
    (net (code "63") (name "Net-(U1-RD1)") (class "Default")
      (node (ref "R39") (pin "1") (pinfunction "1_1") (pintype "passive"))
      (node (ref "U1") (pin "69") (pinfunction "RD1_69") (pintype "bidirectional"))
    )
    (net (code "64") (name "Net-(U1-RD2)") (class "Default")
      (node (ref "R38") (pin "1") (pinfunction "1_1") (pintype "passive"))
      (node (ref "U1") (pin "68") (pinfunction "RD2_68") (pintype "bidirectional"))
    )
    (net (code "65") (name "Net-(U1-VDDCORE{slash}VCAP)") (class "Default")
      (node (ref "C16") (pin "1") (pinfunction "1_1") (pintype "passive"))
      (node (ref "U1") (pin "12") (pinfunction "VDDCORE/VCAP_12") (pintype "power_in"))
    )
    (net (code "66") (name "Net-(U4-CP1)") (class "Default")
      (node (ref "C15") (pin "2") (pinfunction "2_2") (pintype "passive"))
      (node (ref "U4") (pin "20") (pinfunction "CP1_20") (pintype "passive"))
    )
    (net (code "67") (name "Net-(U4-CP2)") (class "Default")
      (node (ref "C15") (pin "1") (pinfunction "1_1") (pintype "passive"))
      (node (ref "U4") (pin "21") (pinfunction "CP2_21") (pintype "passive"))
    )
    (net (code "68") (name "Net-(U4-OUT1A)") (class "Default")
      (node (ref "J1") (pin "1") (pinfunction "1_1") (pintype "passive"))
      (node (ref "U4") (pin "2") (pinfunction "OUT1A_2") (pintype "output"))
    )
    (net (code "69") (name "Net-(U4-OUT1B)") (class "Default")
      (node (ref "J1") (pin "2") (pinfunction "2_2") (pintype "passive"))
      (node (ref "U4") (pin "22") (pinfunction "OUT1B_22") (pintype "output"))
    )
    (net (code "70") (name "Net-(U4-OUT2A)") (class "Default")
      (node (ref "J1") (pin "3") (pinfunction "3_3") (pintype "passive"))
      (node (ref "U4") (pin "11") (pinfunction "OUT2A_11") (pintype "output"))
    )
    (net (code "71") (name "Net-(U4-OUT2B)") (class "Default")
      (node (ref "J1") (pin "4") (pinfunction "4_4") (pintype "passive"))
      (node (ref "U4") (pin "14") (pinfunction "OUT2B_14") (pintype "output"))
    )
    (net (code "72") (name "Net-(U4-Rosc)") (class "Default")
      (node (ref "R13") (pin "2") (pinfunction "2_2") (pintype "passive"))
      (node (ref "U4") (pin "17") (pinfunction "Rosc_17") (pintype "power_in"))
    )
    (net (code "73") (name "Net-(U4-SENSE1)") (class "Default")
      (node (ref "R12") (pin "2") (pinfunction "2_2") (pintype "passive"))
      (node (ref "U4") (pin "1") (pinfunction "SENSE1_1") (pintype "input"))
    )
    (net (code "74") (name "Net-(U4-SENSE2)") (class "Default")
      (node (ref "R11") (pin "2") (pinfunction "2_2") (pintype "passive"))
      (node (ref "U4") (pin "12") (pinfunction "SENSE2_12") (pintype "input"))
    )
    (net (code "75") (name "Net-(U4-VCP)") (class "Default")
      (node (ref "C7") (pin "1") (pinfunction "1_1") (pintype "passive"))
      (node (ref "U4") (pin "19") (pinfunction "VCP_19") (pintype "passive"))
    )
    (net (code "76") (name "Net-(U4-VREG)") (class "Default")
      (node (ref "C14") (pin "2") (pinfunction "2_2") (pintype "passive"))
      (node (ref "U4") (pin "15") (pinfunction "VREG_15") (pintype "passive"))
    )
    (net (code "77") (name "Net-(U5-CP1)") (class "Default")
      (node (ref "C32") (pin "2") (pinfunction "2_2") (pintype "passive"))
      (node (ref "U5") (pin "20") (pinfunction "CP1_20") (pintype "passive"))
    )
    (net (code "78") (name "Net-(U5-CP2)") (class "Default")
      (node (ref "C32") (pin "1") (pinfunction "1_1") (pintype "passive"))
      (node (ref "U5") (pin "21") (pinfunction "CP2_21") (pintype "passive"))
    )
    (net (code "79") (name "Net-(U5-OUT1A)") (class "Default")
      (node (ref "J2") (pin "1") (pinfunction "1_1") (pintype "passive"))
      (node (ref "U5") (pin "2") (pinfunction "OUT1A_2") (pintype "output"))
    )
    (net (code "80") (name "Net-(U5-OUT1B)") (class "Default")
      (node (ref "J2") (pin "2") (pinfunction "2_2") (pintype "passive"))
      (node (ref "U5") (pin "22") (pinfunction "OUT1B_22") (pintype "output"))
    )
    (net (code "81") (name "Net-(U5-OUT2A)") (class "Default")
      (node (ref "J2") (pin "3") (pinfunction "3_3") (pintype "passive"))
      (node (ref "U5") (pin "11") (pinfunction "OUT2A_11") (pintype "output"))
    )
    (net (code "82") (name "Net-(U5-OUT2B)") (class "Default")
      (node (ref "J2") (pin "4") (pinfunction "4_4") (pintype "passive"))
      (node (ref "U5") (pin "14") (pinfunction "OUT2B_14") (pintype "output"))
    )
    (net (code "83") (name "Net-(U5-Rosc)") (class "Default")
      (node (ref "R25") (pin "2") (pinfunction "2_2") (pintype "passive"))
      (node (ref "U5") (pin "17") (pinfunction "Rosc_17") (pintype "power_in"))
    )
    (net (code "84") (name "Net-(U5-SENSE1)") (class "Default")
      (node (ref "R24") (pin "2") (pinfunction "2_2") (pintype "passive"))
      (node (ref "U5") (pin "1") (pinfunction "SENSE1_1") (pintype "input"))
    )
    (net (code "85") (name "Net-(U5-SENSE2)") (class "Default")
      (node (ref "R23") (pin "2") (pinfunction "2_2") (pintype "passive"))
      (node (ref "U5") (pin "12") (pinfunction "SENSE2_12") (pintype "input"))
    )
    (net (code "86") (name "Net-(U5-VCP)") (class "Default")
      (node (ref "C19") (pin "1") (pinfunction "1_1") (pintype "passive"))
      (node (ref "U5") (pin "19") (pinfunction "VCP_19") (pintype "passive"))
    )
    (net (code "87") (name "Net-(U5-VREG)") (class "Default")
      (node (ref "C31") (pin "2") (pinfunction "2_2") (pintype "passive"))
      (node (ref "U5") (pin "15") (pinfunction "VREG_15") (pintype "passive"))
    )
    (net (code "88") (name "Net-(U6-CP1)") (class "Default")
      (node (ref "C40") (pin "2") (pinfunction "2_2") (pintype "passive"))
      (node (ref "U6") (pin "20") (pinfunction "CP1_20") (pintype "passive"))
    )
    (net (code "89") (name "Net-(U6-CP2)") (class "Default")
      (node (ref "C40") (pin "1") (pinfunction "1_1") (pintype "passive"))
      (node (ref "U6") (pin "21") (pinfunction "CP2_21") (pintype "passive"))
    )
    (net (code "90") (name "Net-(U6-OUT1A)") (class "Default")
      (node (ref "J4") (pin "1") (pinfunction "1_1") (pintype "passive"))
      (node (ref "U6") (pin "2") (pinfunction "OUT1A_2") (pintype "output"))
    )
    (net (code "91") (name "Net-(U6-OUT1B)") (class "Default")
      (node (ref "J4") (pin "2") (pinfunction "2_2") (pintype "passive"))
      (node (ref "U6") (pin "22") (pinfunction "OUT1B_22") (pintype "output"))
    )
    (net (code "92") (name "Net-(U6-OUT2A)") (class "Default")
      (node (ref "J4") (pin "3") (pinfunction "3_3") (pintype "passive"))
      (node (ref "U6") (pin "11") (pinfunction "OUT2A_11") (pintype "output"))
    )
    (net (code "93") (name "Net-(U6-OUT2B)") (class "Default")
      (node (ref "J4") (pin "4") (pinfunction "4_4") (pintype "passive"))
      (node (ref "U6") (pin "14") (pinfunction "OUT2B_14") (pintype "output"))
    )
    (net (code "94") (name "Net-(U6-Rosc)") (class "Default")
      (node (ref "R33") (pin "2") (pinfunction "2_2") (pintype "passive"))
      (node (ref "U6") (pin "17") (pinfunction "Rosc_17") (pintype "power_in"))
    )
    (net (code "95") (name "Net-(U6-SENSE1)") (class "Default")
      (node (ref "R32") (pin "2") (pinfunction "2_2") (pintype "passive"))
      (node (ref "U6") (pin "1") (pinfunction "SENSE1_1") (pintype "input"))
    )
    (net (code "96") (name "Net-(U6-SENSE2)") (class "Default")
      (node (ref "R31") (pin "2") (pinfunction "2_2") (pintype "passive"))
      (node (ref "U6") (pin "12") (pinfunction "SENSE2_12") (pintype "input"))
    )
    (net (code "97") (name "Net-(U6-VCP)") (class "Default")
      (node (ref "C33") (pin "1") (pinfunction "1_1") (pintype "passive"))
      (node (ref "U6") (pin "19") (pinfunction "VCP_19") (pintype "passive"))
    )
    (net (code "98") (name "Net-(U6-VREG)") (class "Default")
      (node (ref "C39") (pin "2") (pinfunction "2_2") (pintype "passive"))
      (node (ref "U6") (pin "15") (pinfunction "VREG_15") (pintype "passive"))
    )
    (net (code "99") (name "VCC") (class "Default")
      (node (ref "C20") (pin "1") (pinfunction "1_1") (pintype "passive"))
      (node (ref "C21") (pin "1") (pinfunction "1_1") (pintype "passive"))
      (node (ref "C22") (pin "1") (pinfunction "1_1") (pintype "passive"))
      (node (ref "C23") (pin "1") (pinfunction "1_1") (pintype "passive"))
      (node (ref "C24") (pin "1") (pinfunction "1_1") (pintype "passive"))
      (node (ref "C43") (pin "1") (pinfunction "1_1") (pintype "passive"))
      (node (ref "D1") (pin "2") (pinfunction "K_2") (pintype "passive"))
      (node (ref "J1") (pin "7") (pinfunction "7_7") (pintype "passive"))
      (node (ref "J2") (pin "7") (pinfunction "7_7") (pintype "passive"))
      (node (ref "J4") (pin "7") (pinfunction "7_7") (pintype "passive"))
      (node (ref "L1") (pin "1") (pinfunction "1_1") (pintype "passive"))
      (node (ref "P1") (pin "2") (pinfunction "2_2") (pintype "passive"))
      (node (ref "P2") (pin "1") (pinfunction "1_1") (pintype "passive"))
      (node (ref "R13") (pin "1") (pinfunction "1_1") (pintype "passive"))
      (node (ref "R14") (pin "1") (pinfunction "TOP_1") (pintype "passive"))
      (node (ref "R25") (pin "1") (pinfunction "1_1") (pintype "passive"))
      (node (ref "R27") (pin "1") (pinfunction "TOP_1") (pintype "passive"))
      (node (ref "R33") (pin "1") (pinfunction "1_1") (pintype "passive"))
      (node (ref "R36") (pin "1") (pinfunction "TOP_1") (pintype "passive"))
      (node (ref "R7") (pin "2") (pinfunction "2_2") (pintype "passive"))
      (node (ref "U1") (pin "24") (pinfunction "ENVREG_24") (pintype "input"))
      (node (ref "U1") (pin "25") (pinfunction "AVDD_25") (pintype "power_in"))
      (node (ref "U1") (pin "32") (pinfunction "VDD_32") (pintype "power_in"))
      (node (ref "U1") (pin "48") (pinfunction "VDD_48") (pintype "power_in"))
      (node (ref "U1") (pin "60") (pinfunction "VDDRX_60") (pintype "power_in"))
      (node (ref "U1") (pin "61") (pinfunction "VDDTX_61") (pintype "power_in"))
      (node (ref "U1") (pin "66") (pinfunction "VDDPLL_66") (pintype "power_in"))
      (node (ref "U1") (pin "71") (pinfunction "VDD_71") (pintype "power_in"))
      (node (ref "U2") (pin "4") (pinfunction "OUT_4") (pintype "power_in"))
      (node (ref "U4") (pin "10") (pinfunction "VDD_10") (pintype "power_in"))
      (node (ref "U5") (pin "10") (pinfunction "VDD_10") (pintype "power_in"))
      (node (ref "U6") (pin "10") (pinfunction "VDD_10") (pintype "power_in"))
    )
    (net (code "100") (name "unconnected-(J1-Pad9)") (class "Default")
      (node (ref "J1") (pin "9") (pinfunction "9_9") (pintype "passive"))
    )
    (net (code "101") (name "unconnected-(J2-Pad9)") (class "Default")
      (node (ref "J2") (pin "9") (pinfunction "9_9") (pintype "passive"))
    )
    (net (code "102") (name "unconnected-(J4-Pad9)") (class "Default")
      (node (ref "J4") (pin "9") (pinfunction "9_9") (pintype "passive"))
    )
    (net (code "103") (name "unconnected-(P1-Pad6)") (class "Default")
      (node (ref "P1") (pin "6") (pinfunction "6_6") (pintype "passive"))
    )
    (net (code "104") (name "unconnected-(U1-RA2{slash}AN2{slash}VREF--Pad28)") (class "Default")
      (node (ref "U1") (pin "28") (pinfunction "RA2/AN2/VREF-_28") (pintype "bidirectional"))
    )
    (net (code "105") (name "unconnected-(U1-RA3{slash}AN3{slash}VREF+-Pad27)") (class "Default")
      (node (ref "U1") (pin "27") (pinfunction "RA3/AN3/VREF+_27") (pintype "bidirectional"))
    )
    (net (code "106") (name "unconnected-(U1-RA4{slash}T0CKI-Pad34)") (class "Default")
      (node (ref "U1") (pin "34") (pinfunction "RA4/T0CKI_34") (pintype "bidirectional"))
    )
    (net (code "107") (name "unconnected-(U1-RA5{slash}AN4-Pad33)") (class "Default")
      (node (ref "U1") (pin "33") (pinfunction "RA5/AN4_33") (pintype "bidirectional"))
    )
    (net (code "108") (name "unconnected-(U1-RE6{slash}P1B-Pad74)") (class "Default")
      (node (ref "U1") (pin "74") (pinfunction "RE6/P1B_74") (pintype "bidirectional"))
    )
    (net (code "109") (name "unconnected-(U1-RF1{slash}AN6{slash}C2OUT-Pad23)") (class "Default")
      (node (ref "U1") (pin "23") (pinfunction "RF1/AN6/C2OUT_23") (pintype "bidirectional"))
    )
    (net (code "110") (name "unconnected-(U1-RF6{slash}AN11-Pad14)") (class "Default")
      (node (ref "U1") (pin "14") (pinfunction "RF6/AN11_14") (pintype "bidirectional"))
    )
    (net (code "111") (name "unconnected-(U1-RG1{slash}TX2{slash}CK2-Pad55)") (class "Default")
      (node (ref "U1") (pin "55") (pinfunction "RG1/TX2/CK2_55") (pintype "bidirectional"))
    )
    (net (code "112") (name "unconnected-(U1-RG2{slash}RX2{slash}DT2-Pad42)") (class "Default")
      (node (ref "U1") (pin "42") (pinfunction "RG2/RX2/DT2_42") (pintype "bidirectional"))
    )
    (net (code "113") (name "unconnected-(U1-RH0-Pad79)") (class "Default")
      (node (ref "U1") (pin "79") (pinfunction "RH0_79") (pintype "bidirectional"))
    )
    (net (code "114") (name "unconnected-(U1-RH1-Pad80)") (class "Default")
      (node (ref "U1") (pin "80") (pinfunction "RH1_80") (pintype "bidirectional"))
    )
    (net (code "115") (name "unconnected-(U1-RH2-Pad1)") (class "Default")
      (node (ref "U1") (pin "1") (pinfunction "RH2_1") (pintype "bidirectional"))
    )
    (net (code "116") (name "unconnected-(U1-RH3-Pad2)") (class "Default")
      (node (ref "U1") (pin "2") (pinfunction "RH3_2") (pintype "bidirectional"))
    )
    (net (code "117") (name "unconnected-(U1-RH4{slash}AN12{slash}P3C-Pad22)") (class "Default")
      (node (ref "U1") (pin "22") (pinfunction "RH4/AN12/P3C_22") (pintype "bidirectional"))
    )
    (net (code "118") (name "unconnected-(U1-RH5{slash}AN13{slash}P3B-Pad21)") (class "Default")
      (node (ref "U1") (pin "21") (pinfunction "RH5/AN13/P3B_21") (pintype "bidirectional"))
    )
    (net (code "119") (name "unconnected-(U1-RH6{slash}AN14{slash}P1C-Pad20)") (class "Default")
      (node (ref "U1") (pin "20") (pinfunction "RH6/AN14/P1C_20") (pintype "bidirectional"))
    )
    (net (code "120") (name "unconnected-(U1-RH7{slash}AN15{slash}P1B-Pad19)") (class "Default")
      (node (ref "U1") (pin "19") (pinfunction "RH7/AN15/P1B_19") (pintype "bidirectional"))
    )
    (net (code "121") (name "unconnected-(U1-RJ4-Pad39)") (class "Default")
      (node (ref "U1") (pin "39") (pinfunction "RJ4_39") (pintype "bidirectional"))
    )
    (net (code "122") (name "unconnected-(U1-RJ5-Pad40)") (class "Default")
      (node (ref "U1") (pin "40") (pinfunction "RJ5_40") (pintype "bidirectional"))
    )
  )
)
